# audio_stick_1_0.net
KiCad netlist of a schematic drawn in EAGLE
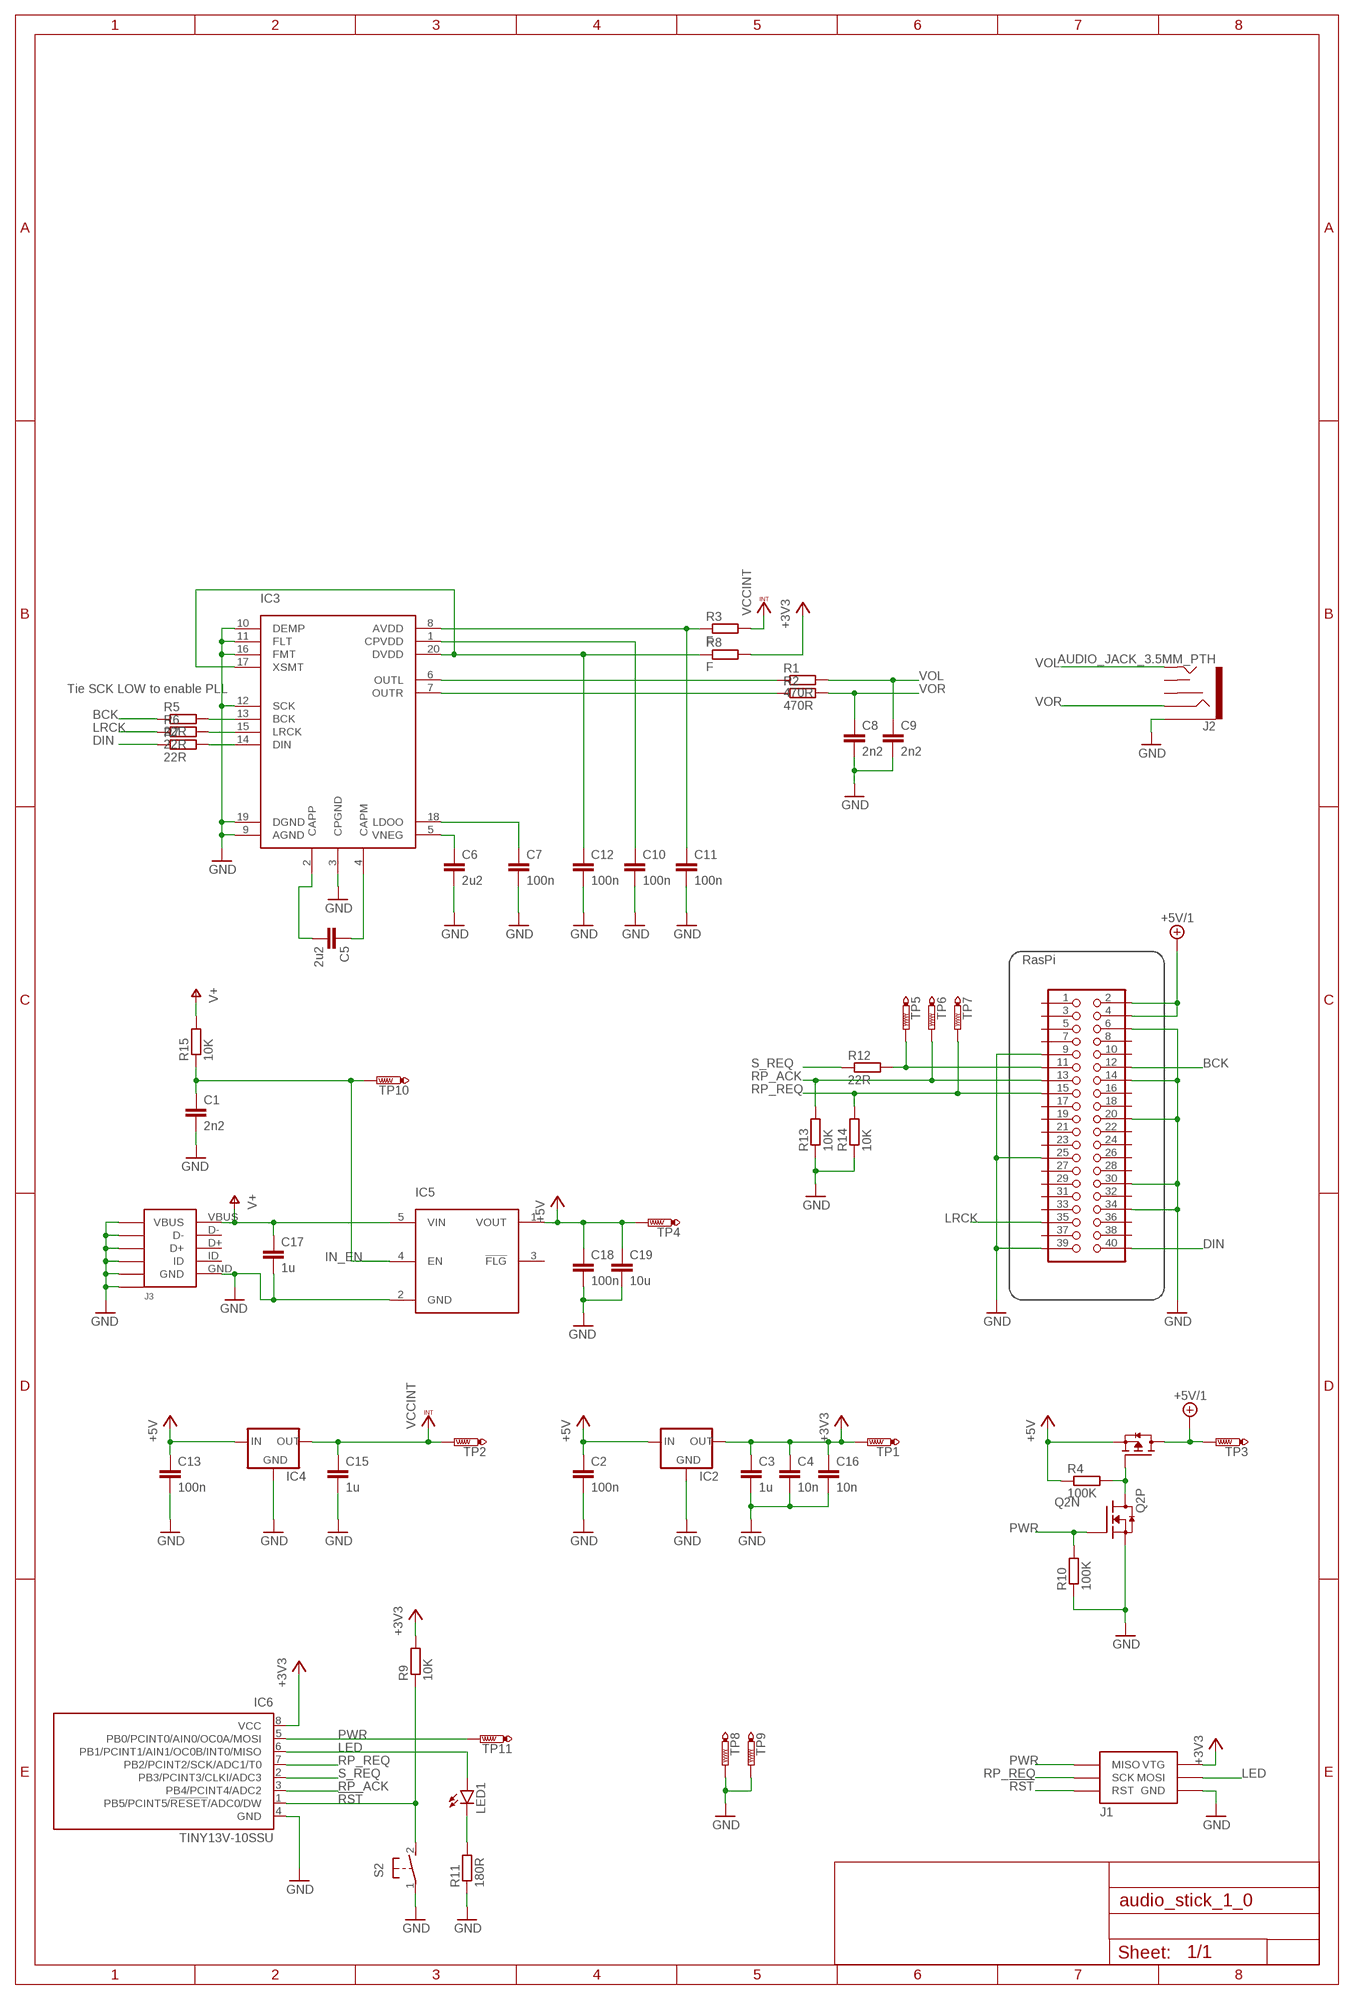
[diagram p0: schematic, sheet 1]

(export (version "E")
  (design (tool "Eeschema 10.0.6"))
  (components
    (comp (ref "C1")
      (value "2n2")
      (footprint "eagle-import:C0603")
      (libsource (lib "eagle-import") (part "C-EUC0603"))
    )
    (comp (ref "C2")
      (value "100n")
      (footprint "eagle-import:C0805")
      (libsource (lib "eagle-import") (part "C-EUC0805"))
    )
    (comp (ref "C3")
      (value "1u")
      (footprint "eagle-import:C0805")
      (libsource (lib "eagle-import") (part "C-EUC0805"))
    )
    (comp (ref "C4")
      (value "10n")
      (footprint "eagle-import:C0805")
      (libsource (lib "eagle-import") (part "C-EUC0805"))
    )
    (comp (ref "C5")
      (value "2u2")
      (footprint "eagle-import:C0603")
      (libsource (lib "eagle-import") (part "C-EUC0603"))
    )
    (comp (ref "C6")
      (value "2u2")
      (footprint "eagle-import:C0603")
      (libsource (lib "eagle-import") (part "C-EUC0603"))
    )
    (comp (ref "C7")
      (value "100n")
      (footprint "eagle-import:C0603")
      (libsource (lib "eagle-import") (part "C-EUC0603"))
    )
    (comp (ref "C8")
      (value "2n2")
      (footprint "eagle-import:C0603")
      (libsource (lib "eagle-import") (part "C-EUC0603"))
    )
    (comp (ref "C9")
      (value "2n2")
      (footprint "eagle-import:C0603")
      (libsource (lib "eagle-import") (part "C-EUC0603"))
    )
    (comp (ref "C10")
      (value "100n")
      (footprint "eagle-import:C0603")
      (libsource (lib "eagle-import") (part "C-EUC0603"))
    )
    (comp (ref "C11")
      (value "100n")
      (footprint "eagle-import:C0603")
      (libsource (lib "eagle-import") (part "C-EUC0603"))
    )
    (comp (ref "C12")
      (value "100n")
      (footprint "eagle-import:C0603")
      (libsource (lib "eagle-import") (part "C-EUC0603"))
    )
    (comp (ref "C13")
      (value "100n")
      (footprint "eagle-import:C0805")
      (libsource (lib "eagle-import") (part "C-EUC0805"))
    )
    (comp (ref "C15")
      (value "1u")
      (footprint "eagle-import:C0805")
      (libsource (lib "eagle-import") (part "C-EUC0805"))
    )
    (comp (ref "C16")
      (value "10n")
      (footprint "eagle-import:C0805")
      (libsource (lib "eagle-import") (part "C-EUC0805"))
    )
    (comp (ref "C17")
      (value "1u")
      (footprint "eagle-import:C0805")
      (libsource (lib "eagle-import") (part "C-EUC0805"))
    )
    (comp (ref "C18")
      (value "100n")
      (footprint "eagle-import:C0603")
      (libsource (lib "eagle-import") (part "C-EUC0603"))
    )
    (comp (ref "C19")
      (value "10u")
      (footprint "eagle-import:C0805")
      (libsource (lib "eagle-import") (part "C-EUC0805"))
    )
    (comp (ref "IC2")
      (value "MCP1700TT")
      (footprint "eagle-import:SOT-23")
      (libsource (lib "eagle-import") (part "MCP1700TT"))
    )
    (comp (ref "IC3")
      (value "PCM5102ASW")
      (footprint "eagle-import:TSSOP20")
      (libsource (lib "eagle-import") (part "PCM5102ASW"))
    )
    (comp (ref "IC4")
      (value "MCP1700TT")
      (footprint "eagle-import:SOT-23")
      (libsource (lib "eagle-import") (part "MCP1700TT"))
    )
    (comp (ref "IC5")
      (value "AP22804W5")
      (footprint "eagle-import:GHI_SOT23-5")
      (libsource (lib "eagle-import") (part "AP22804W5"))
    )
    (comp (ref "IC6")
      (value "TINY13V-10SSU")
      (footprint "eagle-import:8S1")
      (fields (field (name "MPN") "ATTINY13V-10SSU"))
      (libsource (lib "eagle-import") (part "TINY13SSUV-10"))
    )
    (comp (ref "J1")
      (value "AVRISP6TH127")
      (footprint "eagle-import:2X3-50MIL")
      (libsource (lib "eagle-import") (part "AVRISP6TH127"))
    )
    (comp (ref "J2")
      (value "AUDIO_JACK_3.5MM_PTH")
      (footprint "eagle-import:AUDIO-JACK")
      (libsource (lib "eagle-import") (part "AUDIO_JACK_3.5MM_PTH"))
    )
    (comp (ref "J3")
      (value "USB-B")
      (footprint "eagle-import:1050170001")
      (libsource (lib "eagle-import") (part "USB-B"))
    )
    (comp (ref "LED1")
      (value "LED3MM")
      (footprint "eagle-import:LED3MM")
      (libsource (lib "eagle-import") (part "LED3MM"))
    )
    (comp (ref "Q2")
      (value "BSL215")
      (footprint "eagle-import:6TSOP")
      (libsource (lib "eagle-import") (part "BSL215"))
    )
    (comp (ref "R1")
      (value "470R")
      (footprint "eagle-import:R0603")
      (libsource (lib "eagle-import") (part "R-EU_R0603"))
    )
    (comp (ref "R2")
      (value "470R")
      (footprint "eagle-import:R0603")
      (libsource (lib "eagle-import") (part "R-EU_R0603"))
    )
    (comp (ref "R3")
      (value "F")
      (footprint "eagle-import:R0603")
      (libsource (lib "eagle-import") (part "R-EU_R0603"))
    )
    (comp (ref "R4")
      (value "100K")
      (footprint "eagle-import:R0805")
      (libsource (lib "eagle-import") (part "R-EU_R0805"))
    )
    (comp (ref "R5")
      (value "22R")
      (footprint "eagle-import:R0603")
      (libsource (lib "eagle-import") (part "R-EU_R0603"))
    )
    (comp (ref "R6")
      (value "22R")
      (footprint "eagle-import:R0603")
      (libsource (lib "eagle-import") (part "R-EU_R0603"))
    )
    (comp (ref "R7")
      (value "22R")
      (footprint "eagle-import:R0603")
      (libsource (lib "eagle-import") (part "R-EU_R0603"))
    )
    (comp (ref "R8")
      (value "F")
      (footprint "eagle-import:R0603")
      (libsource (lib "eagle-import") (part "R-EU_R0603"))
    )
    (comp (ref "R9")
      (value "10K")
      (footprint "eagle-import:R0603")
      (libsource (lib "eagle-import") (part "R-EU_R0603"))
    )
    (comp (ref "R10")
      (value "100K")
      (footprint "eagle-import:R0805")
      (libsource (lib "eagle-import") (part "R-EU_R0805"))
    )
    (comp (ref "R11")
      (value "180R")
      (footprint "eagle-import:R0805")
      (libsource (lib "eagle-import") (part "R-EU_R0805"))
    )
    (comp (ref "R12")
      (value "22R")
      (footprint "eagle-import:R0603")
      (libsource (lib "eagle-import") (part "R-EU_R0603"))
    )
    (comp (ref "R13")
      (value "10K")
      (footprint "eagle-import:R0603")
      (libsource (lib "eagle-import") (part "R-EU_R0603"))
    )
    (comp (ref "R14")
      (value "10K")
      (footprint "eagle-import:R0603")
      (libsource (lib "eagle-import") (part "R-EU_R0603"))
    )
    (comp (ref "R15")
      (value "10K")
      (footprint "eagle-import:R0603")
      (libsource (lib "eagle-import") (part "R-EU_R0603"))
    )
    (comp (ref "S2")
      (value "31-XX")
      (footprint "eagle-import:B3F-31XX")
      (fields (field (name "MPN") "B3F-3100"))
      (libsource (lib "eagle-import") (part "31-XX"))
    )
    (comp (ref "TP1")
      (value "PTR1PAD1-13")
      (footprint "eagle-import:P1-13")
      (libsource (lib "eagle-import") (part "PTR1PAD1-13"))
    )
    (comp (ref "TP2")
      (value "PTR1PAD1-13")
      (footprint "eagle-import:P1-13")
      (libsource (lib "eagle-import") (part "PTR1PAD1-13"))
    )
    (comp (ref "TP3")
      (value "PTR1PAD1-13")
      (footprint "eagle-import:P1-13")
      (libsource (lib "eagle-import") (part "PTR1PAD1-13"))
    )
    (comp (ref "TP4")
      (value "PTR1PAD1-13")
      (footprint "eagle-import:P1-13")
      (libsource (lib "eagle-import") (part "PTR1PAD1-13"))
    )
    (comp (ref "TP5")
      (value "PTR1PAD1-13")
      (footprint "eagle-import:P1-13")
      (libsource (lib "eagle-import") (part "PTR1PAD1-13"))
    )
    (comp (ref "TP6")
      (value "PTR1PAD1-13")
      (footprint "eagle-import:P1-13")
      (libsource (lib "eagle-import") (part "PTR1PAD1-13"))
    )
    (comp (ref "TP7")
      (value "PTR1PAD1-13")
      (footprint "eagle-import:P1-13")
      (libsource (lib "eagle-import") (part "PTR1PAD1-13"))
    )
    (comp (ref "TP8")
      (value "PTR1PAD1-13")
      (footprint "eagle-import:P1-13")
      (libsource (lib "eagle-import") (part "PTR1PAD1-13"))
    )
    (comp (ref "TP9")
      (value "PTR1PAD1-13")
      (footprint "eagle-import:P1-13")
      (libsource (lib "eagle-import") (part "PTR1PAD1-13"))
    )
    (comp (ref "TP10")
      (value "PTR1PAD1-13")
      (footprint "eagle-import:P1-13")
      (libsource (lib "eagle-import") (part "PTR1PAD1-13"))
    )
    (comp (ref "TP11")
      (value "PTR1PAD1-13")
      (footprint "eagle-import:P1-13")
      (libsource (lib "eagle-import") (part "PTR1PAD1-13"))
    )
    (comp (ref "U$1")
      (value "RASPIZERO")
      (footprint "eagle-import:RASPIZERO")
      (libsource (lib "eagle-import") (part "RASPIZERO"))
    )
  )
  (nets
    (net (code "1") (name "+3V3") (class "Default")
      (node (ref "C16") (pin "1") (pinfunction "1_1") (pintype "passive"))
      (node (ref "C3") (pin "1") (pinfunction "1_1") (pintype "passive"))
      (node (ref "C4") (pin "1") (pinfunction "1_1") (pintype "passive"))
      (node (ref "IC2") (pin "2") (pinfunction "OUT_2") (pintype "passive"))
      (node (ref "IC6") (pin "8") (pinfunction "VCC_8") (pintype "power_in"))
      (node (ref "J1") (pin "2") (pinfunction "VTG_2") (pintype "bidirectional"))
      (node (ref "R8") (pin "2") (pinfunction "2_2") (pintype "passive"))
      (node (ref "R9") (pin "2") (pinfunction "2_2") (pintype "passive"))
      (node (ref "TP1") (pin "TP") (pinfunction "TP_TP") (pintype "input"))
    )
    (net (code "2") (name "+5V") (class "Default")
      (node (ref "C13") (pin "1") (pinfunction "1_1") (pintype "passive"))
      (node (ref "C18") (pin "1") (pinfunction "1_1") (pintype "passive"))
      (node (ref "C19") (pin "1") (pinfunction "1_1") (pintype "passive"))
      (node (ref "C2") (pin "1") (pinfunction "1_1") (pintype "passive"))
      (node (ref "IC2") (pin "3") (pinfunction "IN_3") (pintype "input"))
      (node (ref "IC4") (pin "3") (pinfunction "IN_3") (pintype "input"))
      (node (ref "IC5") (pin "1") (pinfunction "VOUT_1") (pintype "power_in"))
      (node (ref "Q2") (pin "2") (pinfunction "S_2") (pintype "passive"))
      (node (ref "R4") (pin "1") (pinfunction "1_1") (pintype "passive"))
      (node (ref "TP4") (pin "TP") (pinfunction "TP_TP") (pintype "input"))
    )
    (net (code "3") (name "+5V{slash}1") (class "Default")
      (node (ref "Q2") (pin "4") (pinfunction "D_4") (pintype "passive"))
      (node (ref "TP3") (pin "TP") (pinfunction "TP_TP") (pintype "input"))
      (node (ref "U$1") (pin "2") (pinfunction "5V_2") (pintype "passive"))
      (node (ref "U$1") (pin "4") (pinfunction "5V_4") (pintype "passive"))
    )
    (net (code "4") (name "/BCK") (class "Default")
      (node (ref "R5") (pin "1") (pinfunction "1_1") (pintype "passive"))
      (node (ref "U$1") (pin "12") (pinfunction "18_12") (pintype "passive"))
    )
    (net (code "5") (name "/DIN") (class "Default")
      (node (ref "R7") (pin "1") (pinfunction "1_1") (pintype "passive"))
      (node (ref "U$1") (pin "40") (pinfunction "21_40") (pintype "passive"))
    )
    (net (code "6") (name "/IN_EN") (class "Default")
      (node (ref "C1") (pin "1") (pinfunction "1_1") (pintype "passive"))
      (node (ref "IC5") (pin "4") (pinfunction "EN_4") (pintype "input"))
      (node (ref "R15") (pin "1") (pinfunction "1_1") (pintype "passive"))
      (node (ref "TP10") (pin "TP") (pinfunction "TP_TP") (pintype "input"))
    )
    (net (code "7") (name "/LED") (class "Default")
      (node (ref "IC6") (pin "6") (pinfunction "PB1/PCINT1/AIN1/OC0B/INT0/MISO_6") (pintype "bidirectional"))
      (node (ref "J1") (pin "4") (pinfunction "MOSI_4") (pintype "bidirectional"))
      (node (ref "LED1") (pin "A") (pinfunction "A_A") (pintype "passive"))
    )
    (net (code "8") (name "/LRCK") (class "Default")
      (node (ref "R6") (pin "1") (pinfunction "1_1") (pintype "passive"))
      (node (ref "U$1") (pin "35") (pinfunction "19_35") (pintype "passive"))
    )
    (net (code "9") (name "/PWR") (class "Default")
      (node (ref "IC6") (pin "5") (pinfunction "PB0/PCINT0/AIN0/OC0A/MOSI_5") (pintype "bidirectional"))
      (node (ref "J1") (pin "1") (pinfunction "MISO_1") (pintype "bidirectional"))
      (node (ref "Q2") (pin "1") (pinfunction "G_1") (pintype "passive"))
      (node (ref "R10") (pin "2") (pinfunction "2_2") (pintype "passive"))
      (node (ref "TP11") (pin "TP") (pinfunction "TP_TP") (pintype "input"))
    )
    (net (code "10") (name "/RP_ACK") (class "Default")
      (node (ref "IC6") (pin "3") (pinfunction "PB4/PCINT4/ADC2_3") (pintype "bidirectional"))
      (node (ref "R13") (pin "2") (pinfunction "2_2") (pintype "passive"))
      (node (ref "TP6") (pin "TP") (pinfunction "TP_TP") (pintype "input"))
      (node (ref "U$1") (pin "13") (pinfunction "27_13") (pintype "passive"))
    )
    (net (code "11") (name "/RP_REQ") (class "Default")
      (node (ref "IC6") (pin "7") (pinfunction "PB2/PCINT2/SCK/ADC1/T0_7") (pintype "bidirectional"))
      (node (ref "J1") (pin "3") (pinfunction "SCK_3") (pintype "bidirectional"))
      (node (ref "R14") (pin "2") (pinfunction "2_2") (pintype "passive"))
      (node (ref "TP7") (pin "TP") (pinfunction "TP_TP") (pintype "input"))
      (node (ref "U$1") (pin "15") (pinfunction "22_15") (pintype "passive"))
    )
    (net (code "12") (name "/S_REQ") (class "Default")
      (node (ref "IC6") (pin "2") (pinfunction "PB3/PCINT3/CLKI/ADC3_2") (pintype "bidirectional"))
      (node (ref "R12") (pin "1") (pinfunction "1_1") (pintype "passive"))
    )
    (net (code "13") (name "/VOL") (class "Default")
      (node (ref "C9") (pin "1") (pinfunction "1_1") (pintype "passive"))
      (node (ref "J2") (pin "TIP") (pinfunction "TIP_TIP") (pintype "bidirectional"))
      (node (ref "R1") (pin "2") (pinfunction "2_2") (pintype "passive"))
    )
    (net (code "14") (name "/VOR") (class "Default")
      (node (ref "C8") (pin "1") (pinfunction "1_1") (pintype "passive"))
      (node (ref "J2") (pin "RING") (pinfunction "RING_RING") (pintype "bidirectional"))
      (node (ref "R2") (pin "2") (pinfunction "2_2") (pintype "passive"))
    )
    (net (code "15") (name "/~{RST}") (class "Default")
      (node (ref "IC6") (pin "1") (pinfunction "PB5/PCINT5/~{RESET}/ADC0/DW_1") (pintype "bidirectional"))
      (node (ref "J1") (pin "5") (pinfunction "RST_5") (pintype "bidirectional"))
      (node (ref "R9") (pin "1") (pinfunction "1_1") (pintype "passive"))
      (node (ref "S2") (pin "2") (pinfunction "S_2") (pintype "passive"))
    )
    (net (code "16") (name "GND") (class "Default")
      (node (ref "C1") (pin "2") (pinfunction "2_2") (pintype "passive"))
      (node (ref "C10") (pin "2") (pinfunction "2_2") (pintype "passive"))
      (node (ref "C11") (pin "2") (pinfunction "2_2") (pintype "passive"))
      (node (ref "C12") (pin "2") (pinfunction "2_2") (pintype "passive"))
      (node (ref "C13") (pin "2") (pinfunction "2_2") (pintype "passive"))
      (node (ref "C15") (pin "2") (pinfunction "2_2") (pintype "passive"))
      (node (ref "C16") (pin "2") (pinfunction "2_2") (pintype "passive"))
      (node (ref "C17") (pin "2") (pinfunction "2_2") (pintype "passive"))
      (node (ref "C18") (pin "2") (pinfunction "2_2") (pintype "passive"))
      (node (ref "C19") (pin "2") (pinfunction "2_2") (pintype "passive"))
      (node (ref "C2") (pin "2") (pinfunction "2_2") (pintype "passive"))
      (node (ref "C3") (pin "2") (pinfunction "2_2") (pintype "passive"))
      (node (ref "C4") (pin "2") (pinfunction "2_2") (pintype "passive"))
      (node (ref "C6") (pin "2") (pinfunction "2_2") (pintype "passive"))
      (node (ref "C7") (pin "2") (pinfunction "2_2") (pintype "passive"))
      (node (ref "C8") (pin "2") (pinfunction "2_2") (pintype "passive"))
      (node (ref "C9") (pin "2") (pinfunction "2_2") (pintype "passive"))
      (node (ref "IC2") (pin "1") (pinfunction "GND_1") (pintype "input"))
      (node (ref "IC3") (pin "10") (pinfunction "DEMP_10") (pintype "input"))
      (node (ref "IC3") (pin "11") (pinfunction "FLT_11") (pintype "input"))
      (node (ref "IC3") (pin "12") (pinfunction "SCK_12") (pintype "input"))
      (node (ref "IC3") (pin "16") (pinfunction "FMT_16") (pintype "input"))
      (node (ref "IC3") (pin "19") (pinfunction "DGND_19") (pintype "power_in"))
      (node (ref "IC3") (pin "3") (pinfunction "CPGND_3") (pintype "output"))
      (node (ref "IC3") (pin "9") (pinfunction "AGND_9") (pintype "power_in"))
      (node (ref "IC4") (pin "1") (pinfunction "GND_1") (pintype "input"))
      (node (ref "IC5") (pin "2") (pinfunction "GND_2") (pintype "power_in"))
      (node (ref "IC6") (pin "4") (pinfunction "GND_4") (pintype "power_in"))
      (node (ref "J1") (pin "6") (pinfunction "GND_6") (pintype "bidirectional"))
      (node (ref "J2") (pin "SLEEVE") (pinfunction "SLEEVE_SLEEVE") (pintype "bidirectional"))
      (node (ref "J3") (pin "GND") (pinfunction "GND_GND") (pintype "power_in"))
      (node (ref "J3") (pin "P$1") (pinfunction "SH1*4_P$1") (pintype "power_in"))
      (node (ref "J3") (pin "P$10") (pinfunction "SH1*5_P$10") (pintype "power_in"))
      (node (ref "J3") (pin "P$11") (pinfunction "SH1*6_P$11") (pintype "power_in"))
      (node (ref "J3") (pin "P$2") (pinfunction "SH1*1_P$2") (pintype "power_in"))
      (node (ref "J3") (pin "P$3") (pinfunction "SH1*2_P$3") (pintype "power_in"))
      (node (ref "J3") (pin "P$4") (pinfunction "SH1*3_P$4") (pintype "power_in"))
      (node (ref "Q2") (pin "5") (pinfunction "S_5") (pintype "passive"))
      (node (ref "R10") (pin "1") (pinfunction "1_1") (pintype "passive"))
      (node (ref "R11") (pin "1") (pinfunction "1_1") (pintype "passive"))
      (node (ref "R13") (pin "1") (pinfunction "1_1") (pintype "passive"))
      (node (ref "R14") (pin "1") (pinfunction "1_1") (pintype "passive"))
      (node (ref "S2") (pin "1") (pinfunction "P_1") (pintype "passive"))
      (node (ref "TP8") (pin "TP") (pinfunction "TP_TP") (pintype "input"))
      (node (ref "TP9") (pin "TP") (pinfunction "TP_TP") (pintype "input"))
      (node (ref "U$1") (pin "14") (pinfunction "GND_14") (pintype "passive"))
      (node (ref "U$1") (pin "20") (pinfunction "GND_20") (pintype "passive"))
      (node (ref "U$1") (pin "25") (pinfunction "GND_25") (pintype "passive"))
      (node (ref "U$1") (pin "30") (pinfunction "GND_30") (pintype "passive"))
      (node (ref "U$1") (pin "34") (pinfunction "GND_34") (pintype "passive"))
      (node (ref "U$1") (pin "39") (pinfunction "GND_39") (pintype "passive"))
      (node (ref "U$1") (pin "6") (pinfunction "GND_6") (pintype "passive"))
      (node (ref "U$1") (pin "9") (pinfunction "GND_9") (pintype "passive"))
    )
    (net (code "17") (name "Net-(IC3-AVDD)") (class "Default")
      (node (ref "C11") (pin "1") (pinfunction "1_1") (pintype "passive"))
      (node (ref "IC3") (pin "8") (pinfunction "AVDD_8") (pintype "power_in"))
      (node (ref "R3") (pin "1") (pinfunction "1_1") (pintype "passive"))
    )
    (net (code "18") (name "Net-(IC3-BCK)") (class "Default")
      (node (ref "IC3") (pin "13") (pinfunction "BCK_13") (pintype "input"))
      (node (ref "R5") (pin "2") (pinfunction "2_2") (pintype "passive"))
    )
    (net (code "19") (name "Net-(IC3-CAPM)") (class "Default")
      (node (ref "C5") (pin "1") (pinfunction "1_1") (pintype "passive"))
      (node (ref "IC3") (pin "4") (pinfunction "CAPM_4") (pintype "output"))
    )
    (net (code "20") (name "Net-(IC3-CAPP)") (class "Default")
      (node (ref "C5") (pin "2") (pinfunction "2_2") (pintype "passive"))
      (node (ref "IC3") (pin "2") (pinfunction "CAPP_2") (pintype "output"))
    )
    (net (code "21") (name "Net-(IC3-CPVDD)") (class "Default")
      (node (ref "C10") (pin "1") (pinfunction "1_1") (pintype "passive"))
      (node (ref "IC3") (pin "1") (pinfunction "CPVDD_1") (pintype "power_in"))
    )
    (net (code "22") (name "Net-(IC3-DIN)") (class "Default")
      (node (ref "IC3") (pin "14") (pinfunction "DIN_14") (pintype "input"))
      (node (ref "R7") (pin "2") (pinfunction "2_2") (pintype "passive"))
    )
    (net (code "23") (name "Net-(IC3-DVDD)") (class "Default")
      (node (ref "C12") (pin "1") (pinfunction "1_1") (pintype "passive"))
      (node (ref "IC3") (pin "17") (pinfunction "XSMT_17") (pintype "input"))
      (node (ref "IC3") (pin "20") (pinfunction "DVDD_20") (pintype "power_in"))
      (node (ref "R8") (pin "1") (pinfunction "1_1") (pintype "passive"))
    )
    (net (code "24") (name "Net-(IC3-LDOO)") (class "Default")
      (node (ref "C7") (pin "1") (pinfunction "1_1") (pintype "passive"))
      (node (ref "IC3") (pin "18") (pinfunction "LDOO_18") (pintype "power_in"))
    )
    (net (code "25") (name "Net-(IC3-LRCK)") (class "Default")
      (node (ref "IC3") (pin "15") (pinfunction "LRCK_15") (pintype "input"))
      (node (ref "R6") (pin "2") (pinfunction "2_2") (pintype "passive"))
    )
    (net (code "26") (name "Net-(IC3-OUTL)") (class "Default")
      (node (ref "IC3") (pin "6") (pinfunction "OUTL_6") (pintype "output"))
      (node (ref "R1") (pin "1") (pinfunction "1_1") (pintype "passive"))
    )
    (net (code "27") (name "Net-(IC3-OUTR)") (class "Default")
      (node (ref "IC3") (pin "7") (pinfunction "OUTR_7") (pintype "output"))
      (node (ref "R2") (pin "1") (pinfunction "1_1") (pintype "passive"))
    )
    (net (code "28") (name "Net-(IC3-VNEG)") (class "Default")
      (node (ref "C6") (pin "1") (pinfunction "1_1") (pintype "passive"))
      (node (ref "IC3") (pin "5") (pinfunction "VNEG_5") (pintype "power_in"))
    )
    (net (code "29") (name "Net-(LED1-C)") (class "Default")
      (node (ref "LED1") (pin "K") (pinfunction "C_K") (pintype "passive"))
      (node (ref "R11") (pin "2") (pinfunction "2_2") (pintype "passive"))
    )
    (net (code "30") (name "Net-(Q2A-D)") (class "Default")
      (node (ref "Q2") (pin "3") (pinfunction "G_3") (pintype "passive"))
      (node (ref "Q2") (pin "6") (pinfunction "D_6") (pintype "passive"))
      (node (ref "R4") (pin "2") (pinfunction "2_2") (pintype "passive"))
    )
    (net (code "31") (name "Net-(U$1-17)") (class "Default")
      (node (ref "R12") (pin "2") (pinfunction "2_2") (pintype "passive"))
      (node (ref "TP5") (pin "TP") (pinfunction "TP_TP") (pintype "input"))
      (node (ref "U$1") (pin "11") (pinfunction "17_11") (pintype "passive"))
    )
    (net (code "32") (name "V+") (class "Default")
      (node (ref "C17") (pin "1") (pinfunction "1_1") (pintype "passive"))
      (node (ref "IC5") (pin "5") (pinfunction "VIN_5") (pintype "power_in"))
      (node (ref "J3") (pin "VBUS") (pinfunction "VBUS_VBUS") (pintype "power_in"))
      (node (ref "R15") (pin "2") (pinfunction "2_2") (pintype "passive"))
    )
    (net (code "33") (name "VCCINT") (class "Default")
      (node (ref "C15") (pin "1") (pinfunction "1_1") (pintype "passive"))
      (node (ref "IC4") (pin "2") (pinfunction "OUT_2") (pintype "passive"))
      (node (ref "R3") (pin "2") (pinfunction "2_2") (pintype "passive"))
      (node (ref "TP2") (pin "TP") (pinfunction "TP_TP") (pintype "input"))
    )
    (net (code "34") (name "unconnected-(IC5-~{FLG}-Pad3)") (class "Default")
      (node (ref "IC5") (pin "3") (pinfunction "~{FLG}_3") (pintype "open_collector"))
    )
    (net (code "35") (name "unconnected-(J2-PadRSH)") (class "Default")
      (node (ref "J2") (pin "RSH") (pinfunction "RSH_RSH") (pintype "bidirectional"))
    )
    (net (code "36") (name "unconnected-(J2-PadTSH)") (class "Default")
      (node (ref "J2") (pin "TSH") (pinfunction "TSH_TSH") (pintype "bidirectional"))
    )
    (net (code "37") (name "unconnected-(J3-PadD+)") (class "Default")
      (node (ref "J3") (pin "D+") (pinfunction "D+_D+") (pintype "bidirectional"))
    )
    (net (code "38") (name "unconnected-(J3-PadD-)") (class "Default")
      (node (ref "J3") (pin "D-") (pinfunction "D-_D-") (pintype "bidirectional"))
    )
    (net (code "39") (name "unconnected-(J3-PadID)") (class "Default")
      (node (ref "J3") (pin "ID") (pinfunction "ID_ID") (pintype "bidirectional"))
    )
    (net (code "40") (name "unconnected-(U$1-0-Pad27)") (class "Default")
      (node (ref "U$1") (pin "27") (pinfunction "0_27") (pintype "passive"))
    )
    (net (code "41") (name "unconnected-(U$1-1-Pad28)") (class "Default")
      (node (ref "U$1") (pin "28") (pinfunction "1_28") (pintype "passive"))
    )
    (net (code "42") (name "unconnected-(U$1-2-Pad3)") (class "Default")
      (node (ref "U$1") (pin "3") (pinfunction "2_3") (pintype "passive"))
    )
    (net (code "43") (name "unconnected-(U$1-3-Pad5)") (class "Default")
      (node (ref "U$1") (pin "5") (pinfunction "3_5") (pintype "passive"))
    )
    (net (code "44") (name "unconnected-(U$1-3V3-Pad1)") (class "Default")
      (node (ref "U$1") (pin "1") (pinfunction "3V3_1") (pintype "passive"))
    )
    (net (code "45") (name "unconnected-(U$1-3V3-Pad17)") (class "Default")
      (node (ref "U$1") (pin "17") (pinfunction "3V3_17") (pintype "passive"))
    )
    (net (code "46") (name "unconnected-(U$1-4-Pad7)") (class "Default")
      (node (ref "U$1") (pin "7") (pinfunction "4_7") (pintype "passive"))
    )
    (net (code "47") (name "unconnected-(U$1-5-Pad29)") (class "Default")
      (node (ref "U$1") (pin "29") (pinfunction "5_29") (pintype "passive"))
    )
    (net (code "48") (name "unconnected-(U$1-6-Pad31)") (class "Default")
      (node (ref "U$1") (pin "31") (pinfunction "6_31") (pintype "passive"))
    )
    (net (code "49") (name "unconnected-(U$1-7-Pad26)") (class "Default")
      (node (ref "U$1") (pin "26") (pinfunction "7_26") (pintype "passive"))
    )
    (net (code "50") (name "unconnected-(U$1-8-Pad24)") (class "Default")
      (node (ref "U$1") (pin "24") (pinfunction "8_24") (pintype "passive"))
    )
    (net (code "51") (name "unconnected-(U$1-9-Pad21)") (class "Default")
      (node (ref "U$1") (pin "21") (pinfunction "9_21") (pintype "passive"))
    )
    (net (code "52") (name "unconnected-(U$1-10-Pad19)") (class "Default")
      (node (ref "U$1") (pin "19") (pinfunction "10_19") (pintype "passive"))
    )
    (net (code "53") (name "unconnected-(U$1-11-Pad23)") (class "Default")
      (node (ref "U$1") (pin "23") (pinfunction "11_23") (pintype "passive"))
    )
    (net (code "54") (name "unconnected-(U$1-12-Pad32)") (class "Default")
      (node (ref "U$1") (pin "32") (pinfunction "12_32") (pintype "passive"))
    )
    (net (code "55") (name "unconnected-(U$1-13-Pad33)") (class "Default")
      (node (ref "U$1") (pin "33") (pinfunction "13_33") (pintype "passive"))
    )
    (net (code "56") (name "unconnected-(U$1-14-Pad8)") (class "Default")
      (node (ref "U$1") (pin "8") (pinfunction "14_8") (pintype "passive"))
    )
    (net (code "57") (name "unconnected-(U$1-15-Pad10)") (class "Default")
      (node (ref "U$1") (pin "10") (pinfunction "15_10") (pintype "passive"))
    )
    (net (code "58") (name "unconnected-(U$1-16-Pad36)") (class "Default")
      (node (ref "U$1") (pin "36") (pinfunction "16_36") (pintype "passive"))
    )
    (net (code "59") (name "unconnected-(U$1-20-Pad38)") (class "Default")
      (node (ref "U$1") (pin "38") (pinfunction "20_38") (pintype "passive"))
    )
    (net (code "60") (name "unconnected-(U$1-23-Pad16)") (class "Default")
      (node (ref "U$1") (pin "16") (pinfunction "23_16") (pintype "passive"))
    )
    (net (code "61") (name "unconnected-(U$1-24-Pad18)") (class "Default")
      (node (ref "U$1") (pin "18") (pinfunction "24_18") (pintype "passive"))
    )
    (net (code "62") (name "unconnected-(U$1-25-Pad22)") (class "Default")
      (node (ref "U$1") (pin "22") (pinfunction "25_22") (pintype "passive"))
    )
    (net (code "63") (name "unconnected-(U$1-26-Pad37)") (class "Default")
      (node (ref "U$1") (pin "37") (pinfunction "26_37") (pintype "passive"))
    )
  )
)
